# LFSWG.net
KiCad netlist of a schematic drawn in EAGLE
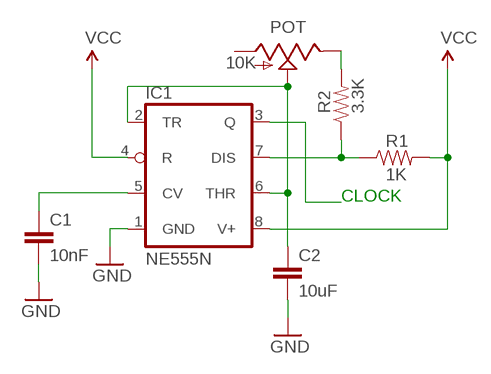
[diagram p0: schematic, sheet 1]

(export (version "E")
  (design (tool "Eeschema 10.0.6"))
  (components
    (comp (ref "C1")
      (value "10nF")
      (footprint "eagle-import:E5-5")
      (libsource (lib "eagle-import") (part "CAP"))
    )
    (comp (ref "C2")
      (value "10uF")
      (footprint "eagle-import:E5-5")
      (libsource (lib "eagle-import") (part "CAP"))
    )
    (comp (ref "IC1")
      (value "NE555N")
      (footprint "eagle-import:DIL08-ROUND")
      (libsource (lib "eagle-import") (part "555NNE"))
    )
    (comp (ref "POT")
      (value "10K")
      (footprint "eagle-import:POT_ALPHA_RV16AF-20")
      (libsource (lib "eagle-import") (part "POT-RV16AF-20"))
    )
    (comp (ref "R1")
      (value "1K")
      (footprint "eagle-import:AXIAL-0.4")
      (libsource (lib "eagle-import") (part "RESISTORPTH-1/4W"))
    )
    (comp (ref "R2")
      (value "3.3K")
      (footprint "eagle-import:AXIAL-0.4")
      (libsource (lib "eagle-import") (part "RESISTORPTH-1/4W"))
    )
  )
  (nets
    (net (code "1") (name "GND") (class "Default")
      (node (ref "C1") (pin "-") (pinfunction "2_-") (pintype "passive"))
      (node (ref "C2") (pin "-") (pinfunction "2_-") (pintype "passive"))
      (node (ref "IC1") (pin "1") (pinfunction "GND_1") (pintype "power_in"))
    )
    (net (code "2") (name "Net-(C1-1)") (class "Default")
      (node (ref "C1") (pin "+") (pinfunction "1_+") (pintype "passive"))
      (node (ref "IC1") (pin "5") (pinfunction "CV_5") (pintype "input"))
    )
    (net (code "3") (name "Net-(C2-1)") (class "Default")
      (node (ref "C2") (pin "+") (pinfunction "1_+") (pintype "passive"))
      (node (ref "IC1") (pin "2") (pinfunction "TR_2") (pintype "input"))
      (node (ref "IC1") (pin "6") (pinfunction "THR_6") (pintype "input"))
      (node (ref "POT") (pin "2") (pinfunction "S_2") (pintype "passive"))
    )
    (net (code "4") (name "Net-(IC1-DIS)") (class "Default")
      (node (ref "IC1") (pin "7") (pinfunction "DIS_7") (pintype "input"))
      (node (ref "R1") (pin "P$1") (pinfunction "1_P$1") (pintype "passive"))
      (node (ref "R2") (pin "P$1") (pinfunction "1_P$1") (pintype "passive"))
    )
    (net (code "5") (name "Net-(POT-E)") (class "Default")
      (node (ref "POT") (pin "3") (pinfunction "E_3") (pintype "passive"))
      (node (ref "R2") (pin "P$2") (pinfunction "2_P$2") (pintype "passive"))
    )
    (net (code "6") (name "VCC") (class "Default")
      (node (ref "IC1") (pin "4") (pinfunction "R_4") (pintype "input"))
      (node (ref "IC1") (pin "8") (pinfunction "V+_8") (pintype "power_in"))
      (node (ref "R1") (pin "P$2") (pinfunction "2_P$2") (pintype "passive"))
    )
    (net (code "7") (name "unconnected-(IC1-Q-Pad3)") (class "Default")
      (node (ref "IC1") (pin "3") (pinfunction "Q_3") (pintype "output"))
    )
    (net (code "8") (name "unconnected-(POT-A-Pad1)") (class "Default")
      (node (ref "POT") (pin "1") (pinfunction "A_1") (pintype "passive"))
    )
  )
)
